# ButtonPad.net
KiCad netlist of a schematic drawn in Altium Designer
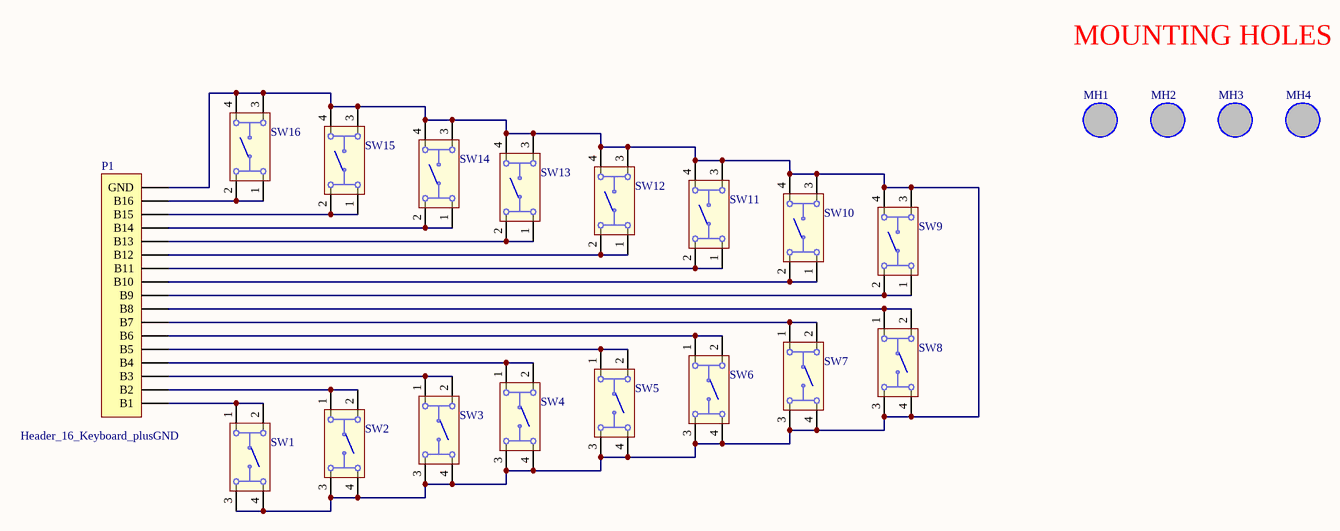
[diagram p0: ButtonPad.SchDoc]

(export (version "E")
  (design (tool "Eeschema 10.0.6"))
  (components
    (comp (ref "MH1")
      (value "Mounting Hole 3.2mm Drill")
      (footprint "MH_3.2MMD")
      (libsource (lib "ButtonPad_lib") (part "MH_3.2MMD"))
    )
    (comp (ref "MH2")
      (value "Mounting Hole 3.2mm Drill")
      (footprint "MH_3.2MMD")
      (libsource (lib "ButtonPad_lib") (part "MH_3.2MMD"))
    )
    (comp (ref "MH3")
      (value "Mounting Hole 3.2mm Drill")
      (footprint "MH_3.2MMD")
      (libsource (lib "ButtonPad_lib") (part "MH_3.2MMD"))
    )
    (comp (ref "MH4")
      (value "Mounting Hole 3.2mm Drill")
      (footprint "MH_3.2MMD")
      (libsource (lib "ButtonPad_lib") (part "MH_3.2MMD"))
    )
    (comp (ref "P1")
      (value "Header_16_Keyboard_plusGND")
      (footprint "HDR1X16_Buttons_plusGND")
      (libsource (lib "ButtonPad_lib") (part "Header_16_Keyboard_plusGND"))
    )
    (comp (ref "SW1")
      (value "430456073736")
      (footprint "430456073736")
      (description "WS-TATV THT Tact Switch 12X12 mm")
      (fields (field (name "MANUFACTURER") "Wuerth Elektronik"))
      (libsource (lib "") (part "430456073736_1"))
    )
    (comp (ref "SW2")
      (value "430456073736")
      (footprint "430456073736")
      (description "WS-TATV THT Tact Switch 12X12 mm")
      (fields (field (name "MANUFACTURER") "Wuerth Elektronik"))
      (libsource (lib "") (part "430456073736_1"))
    )
    (comp (ref "SW3")
      (value "430456073736")
      (footprint "430456073736")
      (description "WS-TATV THT Tact Switch 12X12 mm")
      (fields (field (name "MANUFACTURER") "Wuerth Elektronik"))
      (libsource (lib "") (part "430456073736_1"))
    )
    (comp (ref "SW4")
      (value "430456073736")
      (footprint "430456073736")
      (description "WS-TATV THT Tact Switch 12X12 mm")
      (fields (field (name "MANUFACTURER") "Wuerth Elektronik"))
      (libsource (lib "") (part "430456073736_1"))
    )
    (comp (ref "SW5")
      (value "430456073736")
      (footprint "430456073736")
      (description "WS-TATV THT Tact Switch 12X12 mm")
      (fields (field (name "MANUFACTURER") "Wuerth Elektronik"))
      (libsource (lib "") (part "430456073736_1"))
    )
    (comp (ref "SW6")
      (value "430456073736")
      (footprint "430456073736")
      (description "WS-TATV THT Tact Switch 12X12 mm")
      (fields (field (name "MANUFACTURER") "Wuerth Elektronik"))
      (libsource (lib "") (part "430456073736_1"))
    )
    (comp (ref "SW7")
      (value "430456073736")
      (footprint "430456073736")
      (description "WS-TATV THT Tact Switch 12X12 mm")
      (fields (field (name "MANUFACTURER") "Wuerth Elektronik"))
      (libsource (lib "") (part "430456073736_1"))
    )
    (comp (ref "SW8")
      (value "430456073736")
      (footprint "430456073736")
      (description "WS-TATV THT Tact Switch 12X12 mm")
      (fields (field (name "MANUFACTURER") "Wuerth Elektronik"))
      (libsource (lib "") (part "430456073736_1"))
    )
    (comp (ref "SW9")
      (value "430456073736")
      (footprint "430456073736")
      (description "WS-TATV THT Tact Switch 12X12 mm")
      (fields (field (name "MANUFACTURER") "Wuerth Elektronik"))
      (libsource (lib "ButtonPad_lib") (part "430456073736"))
    )
    (comp (ref "SW10")
      (value "430456073736")
      (footprint "430456073736")
      (description "WS-TATV THT Tact Switch 12X12 mm")
      (fields (field (name "MANUFACTURER") "Wuerth Elektronik"))
      (libsource (lib "ButtonPad_lib") (part "430456073736"))
    )
    (comp (ref "SW11")
      (value "430456073736")
      (footprint "430456073736")
      (description "WS-TATV THT Tact Switch 12X12 mm")
      (fields (field (name "MANUFACTURER") "Wuerth Elektronik"))
      (libsource (lib "ButtonPad_lib") (part "430456073736"))
    )
    (comp (ref "SW12")
      (value "430456073736")
      (footprint "430456073736")
      (description "WS-TATV THT Tact Switch 12X12 mm")
      (fields (field (name "MANUFACTURER") "Wuerth Elektronik"))
      (libsource (lib "ButtonPad_lib") (part "430456073736"))
    )
    (comp (ref "SW13")
      (value "430456073736")
      (footprint "430456073736")
      (description "WS-TATV THT Tact Switch 12X12 mm")
      (fields (field (name "MANUFACTURER") "Wuerth Elektronik"))
      (libsource (lib "ButtonPad_lib") (part "430456073736"))
    )
    (comp (ref "SW14")
      (value "430456073736")
      (footprint "430456073736")
      (description "WS-TATV THT Tact Switch 12X12 mm")
      (fields (field (name "MANUFACTURER") "Wuerth Elektronik"))
      (libsource (lib "ButtonPad_lib") (part "430456073736"))
    )
    (comp (ref "SW15")
      (value "430456073736")
      (footprint "430456073736")
      (description "WS-TATV THT Tact Switch 12X12 mm")
      (fields (field (name "MANUFACTURER") "Wuerth Elektronik"))
      (libsource (lib "ButtonPad_lib") (part "430456073736"))
    )
    (comp (ref "SW16")
      (value "430456073736")
      (footprint "430456073736")
      (description "WS-TATV THT Tact Switch 12X12 mm")
      (fields (field (name "MANUFACTURER") "Wuerth Elektronik"))
      (libsource (lib "ButtonPad_lib") (part "430456073736"))
    )
  )
  (nets
    (net (code "1") (name "Net-(P1-B1)") (class "Default")
      (node (ref "P1") (pin "1") (pinfunction "B1_1") (pintype "passive"))
      (node (ref "SW1") (pin "1") (pinfunction "1_1") (pintype "passive"))
      (node (ref "SW1") (pin "2") (pinfunction "2_2") (pintype "passive"))
    )
    (net (code "2") (name "Net-(P1-B2)") (class "Default")
      (node (ref "P1") (pin "2") (pinfunction "B2_2") (pintype "passive"))
      (node (ref "SW2") (pin "1") (pinfunction "1_1") (pintype "passive"))
      (node (ref "SW2") (pin "2") (pinfunction "2_2") (pintype "passive"))
    )
    (net (code "3") (name "Net-(P1-B3)") (class "Default")
      (node (ref "P1") (pin "3") (pinfunction "B3_3") (pintype "passive"))
      (node (ref "SW3") (pin "1") (pinfunction "1_1") (pintype "passive"))
      (node (ref "SW3") (pin "2") (pinfunction "2_2") (pintype "passive"))
    )
    (net (code "4") (name "Net-(P1-B4)") (class "Default")
      (node (ref "P1") (pin "4") (pinfunction "B4_4") (pintype "passive"))
      (node (ref "SW4") (pin "1") (pinfunction "1_1") (pintype "passive"))
      (node (ref "SW4") (pin "2") (pinfunction "2_2") (pintype "passive"))
    )
    (net (code "5") (name "Net-(P1-B5)") (class "Default")
      (node (ref "P1") (pin "5") (pinfunction "B5_5") (pintype "passive"))
      (node (ref "SW5") (pin "1") (pinfunction "1_1") (pintype "passive"))
      (node (ref "SW5") (pin "2") (pinfunction "2_2") (pintype "passive"))
    )
    (net (code "6") (name "Net-(P1-B6)") (class "Default")
      (node (ref "P1") (pin "6") (pinfunction "B6_6") (pintype "passive"))
      (node (ref "SW6") (pin "1") (pinfunction "1_1") (pintype "passive"))
      (node (ref "SW6") (pin "2") (pinfunction "2_2") (pintype "passive"))
    )
    (net (code "7") (name "Net-(P1-B7)") (class "Default")
      (node (ref "P1") (pin "7") (pinfunction "B7_7") (pintype "passive"))
      (node (ref "SW7") (pin "1") (pinfunction "1_1") (pintype "passive"))
      (node (ref "SW7") (pin "2") (pinfunction "2_2") (pintype "passive"))
    )
    (net (code "8") (name "Net-(P1-B8)") (class "Default")
      (node (ref "P1") (pin "8") (pinfunction "B8_8") (pintype "passive"))
      (node (ref "SW8") (pin "1") (pinfunction "1_1") (pintype "passive"))
      (node (ref "SW8") (pin "2") (pinfunction "2_2") (pintype "passive"))
    )
    (net (code "9") (name "Net-(P1-B9)") (class "Default")
      (node (ref "P1") (pin "9") (pinfunction "B9_9") (pintype "passive"))
      (node (ref "SW9") (pin "1") (pinfunction "1_1") (pintype "passive"))
      (node (ref "SW9") (pin "2") (pinfunction "2_2") (pintype "passive"))
    )
    (net (code "10") (name "Net-(P1-B10)") (class "Default")
      (node (ref "P1") (pin "10") (pinfunction "B10_10") (pintype "passive"))
      (node (ref "SW10") (pin "1") (pinfunction "1_1") (pintype "passive"))
      (node (ref "SW10") (pin "2") (pinfunction "2_2") (pintype "passive"))
    )
    (net (code "11") (name "Net-(P1-B11)") (class "Default")
      (node (ref "P1") (pin "11") (pinfunction "B11_11") (pintype "passive"))
      (node (ref "SW11") (pin "1") (pinfunction "1_1") (pintype "passive"))
      (node (ref "SW11") (pin "2") (pinfunction "2_2") (pintype "passive"))
    )
    (net (code "12") (name "Net-(P1-B12)") (class "Default")
      (node (ref "P1") (pin "12") (pinfunction "B12_12") (pintype "passive"))
      (node (ref "SW12") (pin "1") (pinfunction "1_1") (pintype "passive"))
      (node (ref "SW12") (pin "2") (pinfunction "2_2") (pintype "passive"))
    )
    (net (code "13") (name "Net-(P1-B13)") (class "Default")
      (node (ref "P1") (pin "13") (pinfunction "B13_13") (pintype "passive"))
      (node (ref "SW13") (pin "1") (pinfunction "1_1") (pintype "passive"))
      (node (ref "SW13") (pin "2") (pinfunction "2_2") (pintype "passive"))
    )
    (net (code "14") (name "Net-(P1-B14)") (class "Default")
      (node (ref "P1") (pin "14") (pinfunction "B14_14") (pintype "passive"))
      (node (ref "SW14") (pin "1") (pinfunction "1_1") (pintype "passive"))
      (node (ref "SW14") (pin "2") (pinfunction "2_2") (pintype "passive"))
    )
    (net (code "15") (name "Net-(P1-B15)") (class "Default")
      (node (ref "P1") (pin "15") (pinfunction "B15_15") (pintype "passive"))
      (node (ref "SW15") (pin "1") (pinfunction "1_1") (pintype "passive"))
      (node (ref "SW15") (pin "2") (pinfunction "2_2") (pintype "passive"))
    )
    (net (code "16") (name "Net-(P1-B16)") (class "Default")
      (node (ref "P1") (pin "16") (pinfunction "B16_16") (pintype "passive"))
      (node (ref "SW16") (pin "1") (pinfunction "1_1") (pintype "passive"))
      (node (ref "SW16") (pin "2") (pinfunction "2_2") (pintype "passive"))
    )
    (net (code "17") (name "Net-(P1-GND)") (class "Default")
      (node (ref "P1") (pin "17") (pinfunction "GND_17") (pintype "passive"))
      (node (ref "SW1") (pin "3") (pinfunction "3_3") (pintype "passive"))
      (node (ref "SW1") (pin "4") (pinfunction "4_4") (pintype "passive"))
      (node (ref "SW10") (pin "3") (pinfunction "3_3") (pintype "passive"))
      (node (ref "SW10") (pin "4") (pinfunction "4_4") (pintype "passive"))
      (node (ref "SW11") (pin "3") (pinfunction "3_3") (pintype "passive"))
      (node (ref "SW11") (pin "4") (pinfunction "4_4") (pintype "passive"))
      (node (ref "SW12") (pin "3") (pinfunction "3_3") (pintype "passive"))
      (node (ref "SW12") (pin "4") (pinfunction "4_4") (pintype "passive"))
      (node (ref "SW13") (pin "3") (pinfunction "3_3") (pintype "passive"))
      (node (ref "SW13") (pin "4") (pinfunction "4_4") (pintype "passive"))
      (node (ref "SW14") (pin "3") (pinfunction "3_3") (pintype "passive"))
      (node (ref "SW14") (pin "4") (pinfunction "4_4") (pintype "passive"))
      (node (ref "SW15") (pin "3") (pinfunction "3_3") (pintype "passive"))
      (node (ref "SW15") (pin "4") (pinfunction "4_4") (pintype "passive"))
      (node (ref "SW16") (pin "3") (pinfunction "3_3") (pintype "passive"))
      (node (ref "SW16") (pin "4") (pinfunction "4_4") (pintype "passive"))
      (node (ref "SW2") (pin "3") (pinfunction "3_3") (pintype "passive"))
      (node (ref "SW2") (pin "4") (pinfunction "4_4") (pintype "passive"))
      (node (ref "SW3") (pin "3") (pinfunction "3_3") (pintype "passive"))
      (node (ref "SW3") (pin "4") (pinfunction "4_4") (pintype "passive"))
      (node (ref "SW4") (pin "3") (pinfunction "3_3") (pintype "passive"))
      (node (ref "SW4") (pin "4") (pinfunction "4_4") (pintype "passive"))
      (node (ref "SW5") (pin "3") (pinfunction "3_3") (pintype "passive"))
      (node (ref "SW5") (pin "4") (pinfunction "4_4") (pintype "passive"))
      (node (ref "SW6") (pin "3") (pinfunction "3_3") (pintype "passive"))
      (node (ref "SW6") (pin "4") (pinfunction "4_4") (pintype "passive"))
      (node (ref "SW7") (pin "3") (pinfunction "3_3") (pintype "passive"))
      (node (ref "SW7") (pin "4") (pinfunction "4_4") (pintype "passive"))
      (node (ref "SW8") (pin "3") (pinfunction "3_3") (pintype "passive"))
      (node (ref "SW8") (pin "4") (pinfunction "4_4") (pintype "passive"))
      (node (ref "SW9") (pin "3") (pinfunction "3_3") (pintype "passive"))
      (node (ref "SW9") (pin "4") (pinfunction "4_4") (pintype "passive"))
    )
  )
)
